# 1_Power.net
KiCad netlist of a schematic drawn in Altium Designer
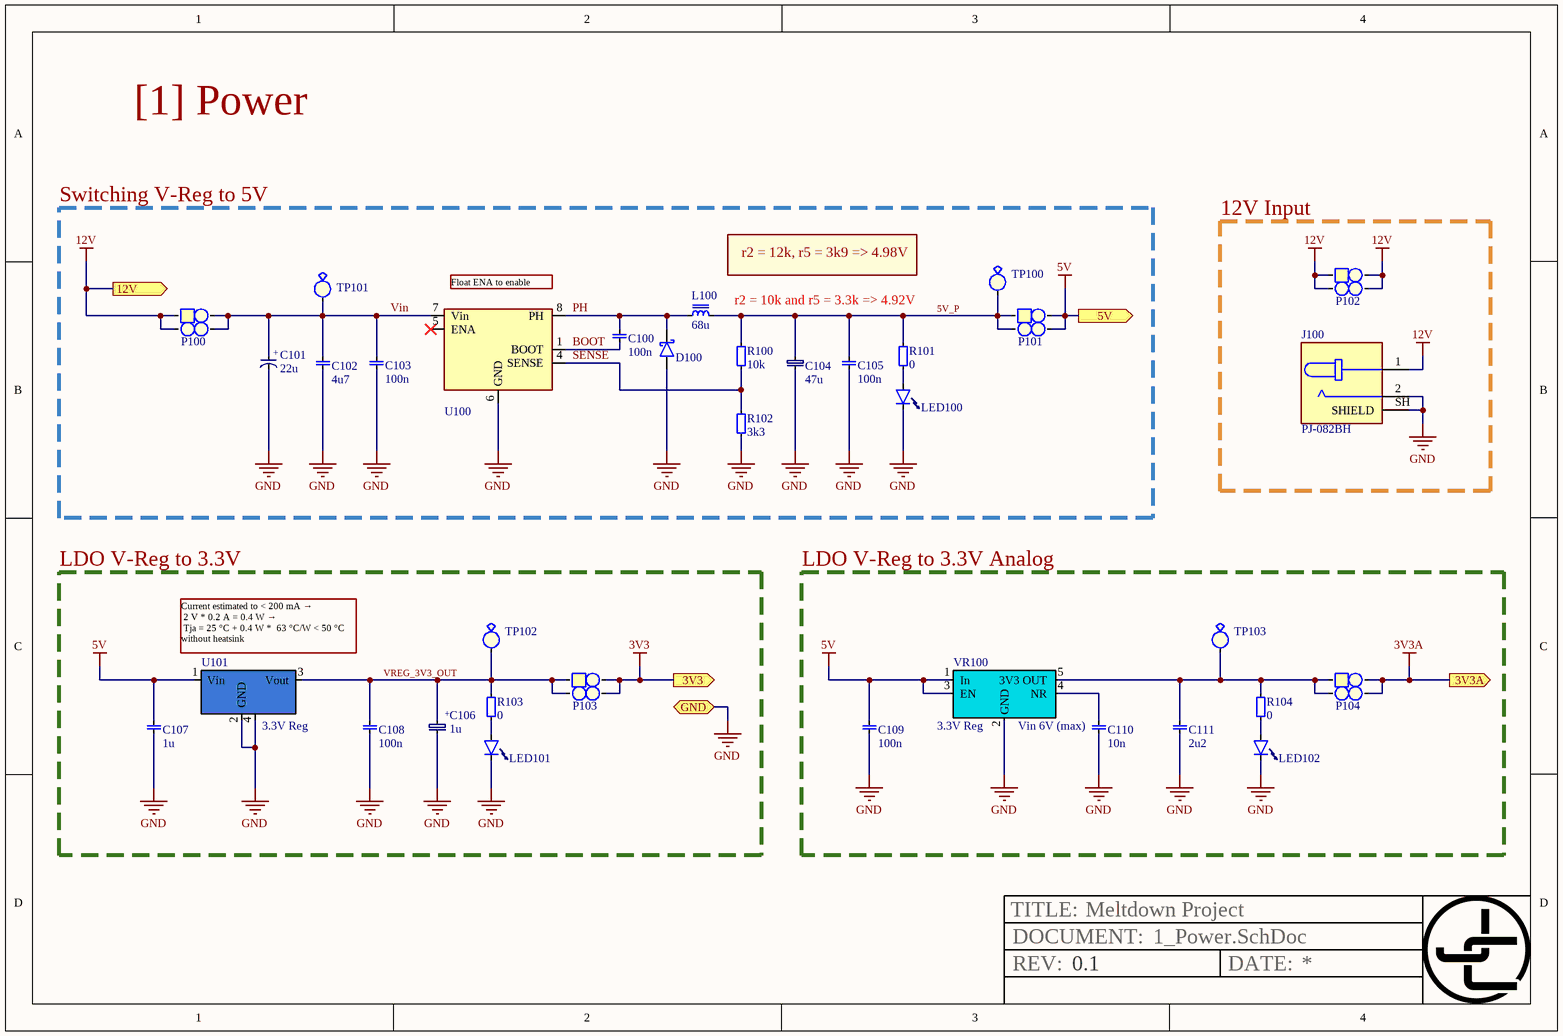
[diagram p0: 1_Power.SchDoc]

(export (version "E")
  (design (tool "Eeschema 10.0.6"))
  (components
    (comp (ref "C100")
      (value "100n")
      (footprint "1210, cap")
      (fields (field (name "Comment") "1210, capacitor"))
      (libsource (lib "jclib") (part "1210, capacitor"))
    )
    (comp (ref "C101")
      (value "22u")
      (footprint "EEEFT1E220AR")
      (fields (field (name "Comment") "cap, Electrolyt Case B"))
      (libsource (lib "jclib") (part "cap, Electrolyt Case B"))
    )
    (comp (ref "C102")
      (value "4u7")
      (footprint "1812, cap")
      (fields (field (name "PART NUMBER") "C1812C475K5RACTU") (field (name "Comment") "1812, capacitor"))
      (libsource (lib "jclib") (part "1812, capacitor"))
    )
    (comp (ref "C103")
      (value "100n")
      (footprint "1210, cap")
      (fields (field (name "Comment") "1210, capacitor"))
      (libsource (lib "jclib") (part "1210, capacitor"))
    )
    (comp (ref "C104")
      (value "47u")
      (footprint "CASE_E")
      (description "Tantalum")
      (fields (field (name "PART NUMBER") "TPSE476K020R0200") (field (name "Comment") "cap, Case E"))
      (libsource (lib "jclib") (part "cap, Case E"))
    )
    (comp (ref "C105")
      (value "100n")
      (footprint "1210, cap")
      (fields (field (name "Comment") "1210, capacitor"))
      (libsource (lib "jclib") (part "1210, capacitor"))
    )
    (comp (ref "C106")
      (value "1u")
      (footprint "CASE_B")
      (fields (field (name "Comment") "Cap, case B"))
      (libsource (lib "jclib") (part "Cap, case B"))
    )
    (comp (ref "C107")
      (value "1u")
      (footprint "0603 cap")
      (fields (field (name "Comment") "0603, capacitor"))
      (libsource (lib "jclib") (part "0603, capacitor"))
    )
    (comp (ref "C108")
      (value "100n")
      (footprint "0603 cap")
      (fields (field (name "Comment") "0603, capacitor"))
      (libsource (lib "jclib") (part "0603, capacitor"))
    )
    (comp (ref "C109")
      (value "100n")
      (footprint "0603 cap")
      (fields (field (name "Comment") "0603, capacitor"))
      (libsource (lib "jclib") (part "0603, capacitor"))
    )
    (comp (ref "C110")
      (value "10n")
      (footprint "0603 cap")
      (fields (field (name "Comment") "0603, capacitor"))
      (libsource (lib "jclib") (part "0603, capacitor"))
    )
    (comp (ref "C111")
      (value "2u2")
      (footprint "0603 cap")
      (fields (field (name "Comment") "0603, capacitor"))
      (libsource (lib "jclib") (part "0603, capacitor"))
    )
    (comp (ref "D100")
      (value "B340A-E3/61T")
      (footprint "DO-214AC")
      (description "SchottkydiodE, 40 V, 3 A")
      (libsource (lib "jclib") (part "B340A-E3/61T"))
    )
    (comp (ref "J100")
      (value "PJ-082BH")
      (footprint "CUI_PJ-082BH")
      (description "2.5 x 6.5 mm, 10.0 A, Horizontal, Through Hole, Shielded, Dc Power Jack Connector")
      (fields (field (name "MF") "CUI Devices"))
      (libsource (lib "jclib") (part "Power Jack"))
    )
    (comp (ref "L100")
      (value "68u")
      (footprint "MSS1260")
      (description "68 µH, 2.3 A,")
      (fields (field (name "PART NUMBER") "SRR1260-680M") (field (name "Comment") "Coil, MSS1260"))
      (libsource (lib "jclib") (part "Coil, MSS1260"))
    )
    (comp (ref "LED100")
      (value "0603, LED")
      (footprint "0603 LED")
      (libsource (lib "jclib") (part "0603, LED"))
    )
    (comp (ref "LED101")
      (value "0603, LED")
      (footprint "0603 LED")
      (libsource (lib "jclib") (part "0603, LED"))
    )
    (comp (ref "LED102")
      (value "0603, LED")
      (footprint "0603 LED")
      (libsource (lib "jclib") (part "0603, LED"))
    )
    (comp (ref "P100")
      (value "2x2 Pin Header")
      (footprint "2x2 PH")
      (libsource (lib "jclib") (part "2x2 Pin Header"))
    )
    (comp (ref "P101")
      (value "2x2 Pin Header")
      (footprint "2x2 PH")
      (libsource (lib "jclib") (part "2x2 Pin Header"))
    )
    (comp (ref "P102")
      (value "2x2 Pin Header")
      (footprint "2x2 PH")
      (libsource (lib "jclib") (part "2x2 Pin Header"))
    )
    (comp (ref "P103")
      (value "2x2 Pin Header")
      (footprint "2x2 PH")
      (libsource (lib "jclib") (part "2x2 Pin Header"))
    )
    (comp (ref "P104")
      (value "2x2 Pin Header")
      (footprint "2x2 PH")
      (libsource (lib "jclib") (part "2x2 Pin Header"))
    )
    (comp (ref "R100")
      (value "10k")
      (footprint "0603")
      (fields (field (name "Comment") "0603, resistor"))
      (libsource (lib "jclib") (part "0603, resistor"))
    )
    (comp (ref "R101")
      (value "0")
      (footprint "0603")
      (fields (field (name "Comment") "0603, resistor"))
      (libsource (lib "jclib") (part "0603, resistor"))
    )
    (comp (ref "R102")
      (value "3k3")
      (footprint "0603")
      (fields (field (name "Comment") "0603, resistor"))
      (libsource (lib "jclib") (part "0603, resistor"))
    )
    (comp (ref "R103")
      (value "0")
      (footprint "0603")
      (fields (field (name "Comment") "0603, resistor"))
      (libsource (lib "jclib") (part "0603, resistor"))
    )
    (comp (ref "R104")
      (value "0")
      (footprint "0603")
      (fields (field (name "Comment") "0603, resistor"))
      (libsource (lib "jclib") (part "0603, resistor"))
    )
    (comp (ref "TP100")
      (value "Test Point")
      (footprint "testPoint")
      (libsource (lib "jclib") (part "Test Point"))
    )
    (comp (ref "TP101")
      (value "Test Point")
      (footprint "testPoint")
      (libsource (lib "jclib") (part "Test Point"))
    )
    (comp (ref "TP102")
      (value "Test Point")
      (footprint "testPoint")
      (libsource (lib "jclib") (part "Test Point"))
    )
    (comp (ref "TP103")
      (value "Test Point")
      (footprint "testPoint")
      (libsource (lib "jclib") (part "Test Point"))
    )
    (comp (ref "U100")
      (value "TPS5410")
      (footprint "SOIC8")
      (description "1-A, Wide Input Range, Step-Down Converter")
      (libsource (lib "jclib") (part "TPS5410"))
    )
    (comp (ref "U101")
      (value "3.3V Reg")
      (footprint "SOT223")
      (description "1 A, Positive Fixed-Voltage, Low-ccDropout Regulator")
      (libsource (lib "jclib") (part "MCP1826S"))
    )
    (comp (ref "VR100")
      (value "3.3V Reg")
      (footprint "SOT23-5")
      (description "3.3V Reg, Ultra-Low Noise, 200 mA")
      (fields (field (name "INPUT VOLTAGE") "Vin 6V (max)"))
      (libsource (lib "jclib") (part "TPS79333DBR"))
    )
  )
  (nets
    (net (code "1") (name "/5V_P") (class "Default")
      (node (ref "C104") (pin "1") (pinfunction "1_1") (pintype "passive"))
      (node (ref "C105") (pin "1") (pinfunction "1_1") (pintype "passive"))
      (node (ref "L100") (pin "1") (pinfunction "1_1") (pintype "passive"))
      (node (ref "P101") (pin "1") (pinfunction "1_1") (pintype "passive"))
      (node (ref "P101") (pin "2") (pinfunction "2_2") (pintype "passive"))
      (node (ref "R100") (pin "0") (pinfunction "0_0") (pintype "passive"))
      (node (ref "R101") (pin "0") (pinfunction "0_0") (pintype "passive"))
      (node (ref "TP100") (pin "0") (pinfunction "0_0") (pintype "passive"))
    )
    (net (code "2") (name "/BOOT") (class "Default")
      (node (ref "C100") (pin "0") (pinfunction "0_0") (pintype "passive"))
      (node (ref "U100") (pin "1") (pinfunction "BOOT_1") (pintype "passive"))
    )
    (net (code "3") (name "/PH") (class "Default")
      (node (ref "C100") (pin "1") (pinfunction "1_1") (pintype "passive"))
      (node (ref "D100") (pin "1") (pinfunction "K_1") (pintype "passive"))
      (node (ref "L100") (pin "2") (pinfunction "2_2") (pintype "passive"))
      (node (ref "U100") (pin "8") (pinfunction "PH_8") (pintype "passive"))
    )
    (net (code "4") (name "/SENSE") (class "Default")
      (node (ref "R100") (pin "1") (pinfunction "1_1") (pintype "passive"))
      (node (ref "R102") (pin "0") (pinfunction "0_0") (pintype "passive"))
      (node (ref "U100") (pin "4") (pinfunction "SENSE_4") (pintype "passive"))
    )
    (net (code "5") (name "/VREG_3V3_OUT") (class "Default")
      (node (ref "C106") (pin "2") (pinfunction "2_2") (pintype "passive"))
      (node (ref "C108") (pin "1") (pinfunction "1_1") (pintype "passive"))
      (node (ref "P103") (pin "1") (pinfunction "1_1") (pintype "passive"))
      (node (ref "P103") (pin "2") (pinfunction "2_2") (pintype "passive"))
      (node (ref "R103") (pin "0") (pinfunction "0_0") (pintype "passive"))
      (node (ref "TP102") (pin "0") (pinfunction "0_0") (pintype "passive"))
      (node (ref "U101") (pin "3") (pinfunction "Vout_3") (pintype "passive"))
    )
    (net (code "6") (name "/Vin") (class "Default")
      (node (ref "C101") (pin "2") (pinfunction "2_2") (pintype "passive"))
      (node (ref "C102") (pin "1") (pinfunction "1_1") (pintype "passive"))
      (node (ref "C103") (pin "1") (pinfunction "1_1") (pintype "passive"))
      (node (ref "P100") (pin "3") (pinfunction "3_3") (pintype "passive"))
      (node (ref "P100") (pin "4") (pinfunction "4_4") (pintype "passive"))
      (node (ref "TP101") (pin "0") (pinfunction "0_0") (pintype "passive"))
      (node (ref "U100") (pin "7") (pinfunction "Vin_7") (pintype "passive"))
    )
    (net (code "7") (name "3V3") (class "Default")
      (node (ref "P103") (pin "3") (pinfunction "3_3") (pintype "passive"))
      (node (ref "P103") (pin "4") (pinfunction "4_4") (pintype "passive"))
    )
    (net (code "8") (name "3V3A") (class "Default")
      (node (ref "P104") (pin "3") (pinfunction "3_3") (pintype "passive"))
      (node (ref "P104") (pin "4") (pinfunction "4_4") (pintype "passive"))
    )
    (net (code "9") (name "5V") (class "Default")
      (node (ref "C107") (pin "1") (pinfunction "1_1") (pintype "passive"))
      (node (ref "C109") (pin "1") (pinfunction "1_1") (pintype "passive"))
      (node (ref "P101") (pin "3") (pinfunction "3_3") (pintype "passive"))
      (node (ref "P101") (pin "4") (pinfunction "4_4") (pintype "passive"))
      (node (ref "U101") (pin "1") (pinfunction "Vin_1") (pintype "passive"))
      (node (ref "VR100") (pin "1") (pinfunction "In_1") (pintype "passive"))
      (node (ref "VR100") (pin "3") (pinfunction "EN_3") (pintype "passive"))
    )
    (net (code "10") (name "12V") (class "Default")
      (node (ref "J100") (pin "1") (pinfunction "1_1") (pintype "passive"))
      (node (ref "P100") (pin "1") (pinfunction "1_1") (pintype "passive"))
      (node (ref "P100") (pin "2") (pinfunction "2_2") (pintype "passive"))
      (node (ref "P102") (pin "1") (pinfunction "1_1") (pintype "passive"))
      (node (ref "P102") (pin "2") (pinfunction "2_2") (pintype "passive"))
      (node (ref "P102") (pin "3") (pinfunction "3_3") (pintype "passive"))
      (node (ref "P102") (pin "4") (pinfunction "4_4") (pintype "passive"))
    )
    (net (code "11") (name "GND") (class "Default")
      (node (ref "C101") (pin "1") (pinfunction "1_1") (pintype "passive"))
      (node (ref "C102") (pin "0") (pinfunction "0_0") (pintype "passive"))
      (node (ref "C103") (pin "0") (pinfunction "0_0") (pintype "passive"))
      (node (ref "C104") (pin "2") (pinfunction "2_2") (pintype "passive"))
      (node (ref "C105") (pin "0") (pinfunction "0_0") (pintype "passive"))
      (node (ref "C106") (pin "1") (pinfunction "1_1") (pintype "passive"))
      (node (ref "C107") (pin "0") (pinfunction "0_0") (pintype "passive"))
      (node (ref "C108") (pin "0") (pinfunction "0_0") (pintype "passive"))
      (node (ref "C109") (pin "0") (pinfunction "0_0") (pintype "passive"))
      (node (ref "C110") (pin "0") (pinfunction "0_0") (pintype "passive"))
      (node (ref "C111") (pin "0") (pinfunction "0_0") (pintype "passive"))
      (node (ref "D100") (pin "2") (pinfunction "A_2") (pintype "passive"))
      (node (ref "J100") (pin "2") (pinfunction "2_2") (pintype "passive"))
      (node (ref "J100") (pin "SH") (pinfunction "SHIELD_SH") (pintype "passive"))
      (node (ref "LED100") (pin "0") (pinfunction "Cathode_0") (pintype "passive"))
      (node (ref "LED101") (pin "0") (pinfunction "Cathode_0") (pintype "passive"))
      (node (ref "LED102") (pin "0") (pinfunction "Cathode_0") (pintype "passive"))
      (node (ref "R102") (pin "1") (pinfunction "1_1") (pintype "passive"))
      (node (ref "U100") (pin "6") (pinfunction "GND_6") (pintype "passive"))
      (node (ref "U101") (pin "2") (pinfunction "GND_2") (pintype "passive"))
      (node (ref "U101") (pin "4") (pintype "passive"))
      (node (ref "VR100") (pin "2") (pinfunction "GND_2") (pintype "passive"))
    )
    (net (code "12") (name "Net-(LED100-Pad1)") (class "Default")
      (node (ref "LED100") (pin "1") (pinfunction "1_1") (pintype "passive"))
      (node (ref "R101") (pin "1") (pinfunction "1_1") (pintype "passive"))
    )
    (net (code "13") (name "Net-(LED101-Pad1)") (class "Default")
      (node (ref "LED101") (pin "1") (pinfunction "1_1") (pintype "passive"))
      (node (ref "R103") (pin "1") (pinfunction "1_1") (pintype "passive"))
    )
    (net (code "14") (name "Net-(LED102-Pad1)") (class "Default")
      (node (ref "LED102") (pin "1") (pinfunction "1_1") (pintype "passive"))
      (node (ref "R104") (pin "1") (pinfunction "1_1") (pintype "passive"))
    )
    (net (code "15") (name "Net-(VR100-3V3_OUT)") (class "Default")
      (node (ref "C111") (pin "1") (pinfunction "1_1") (pintype "passive"))
      (node (ref "P104") (pin "1") (pinfunction "1_1") (pintype "passive"))
      (node (ref "P104") (pin "2") (pinfunction "2_2") (pintype "passive"))
      (node (ref "R104") (pin "0") (pinfunction "0_0") (pintype "passive"))
      (node (ref "TP103") (pin "0") (pinfunction "0_0") (pintype "passive"))
      (node (ref "VR100") (pin "5") (pinfunction "3V3_OUT_5") (pintype "passive"))
    )
    (net (code "16") (name "Net-(VR100-NR)") (class "Default")
      (node (ref "C110") (pin "1") (pinfunction "1_1") (pintype "passive"))
      (node (ref "VR100") (pin "4") (pinfunction "NR_4") (pintype "passive"))
    )
    (net (code "17") (name "unconnected-(U100-ENA-Pad5)") (class "Default")
      (node (ref "U100") (pin "5") (pinfunction "ENA_5") (pintype "passive+no_connect"))
    )
  )
)
